# ESP32_led_flasher_3.net
KiCad netlist of a schematic drawn in EAGLE
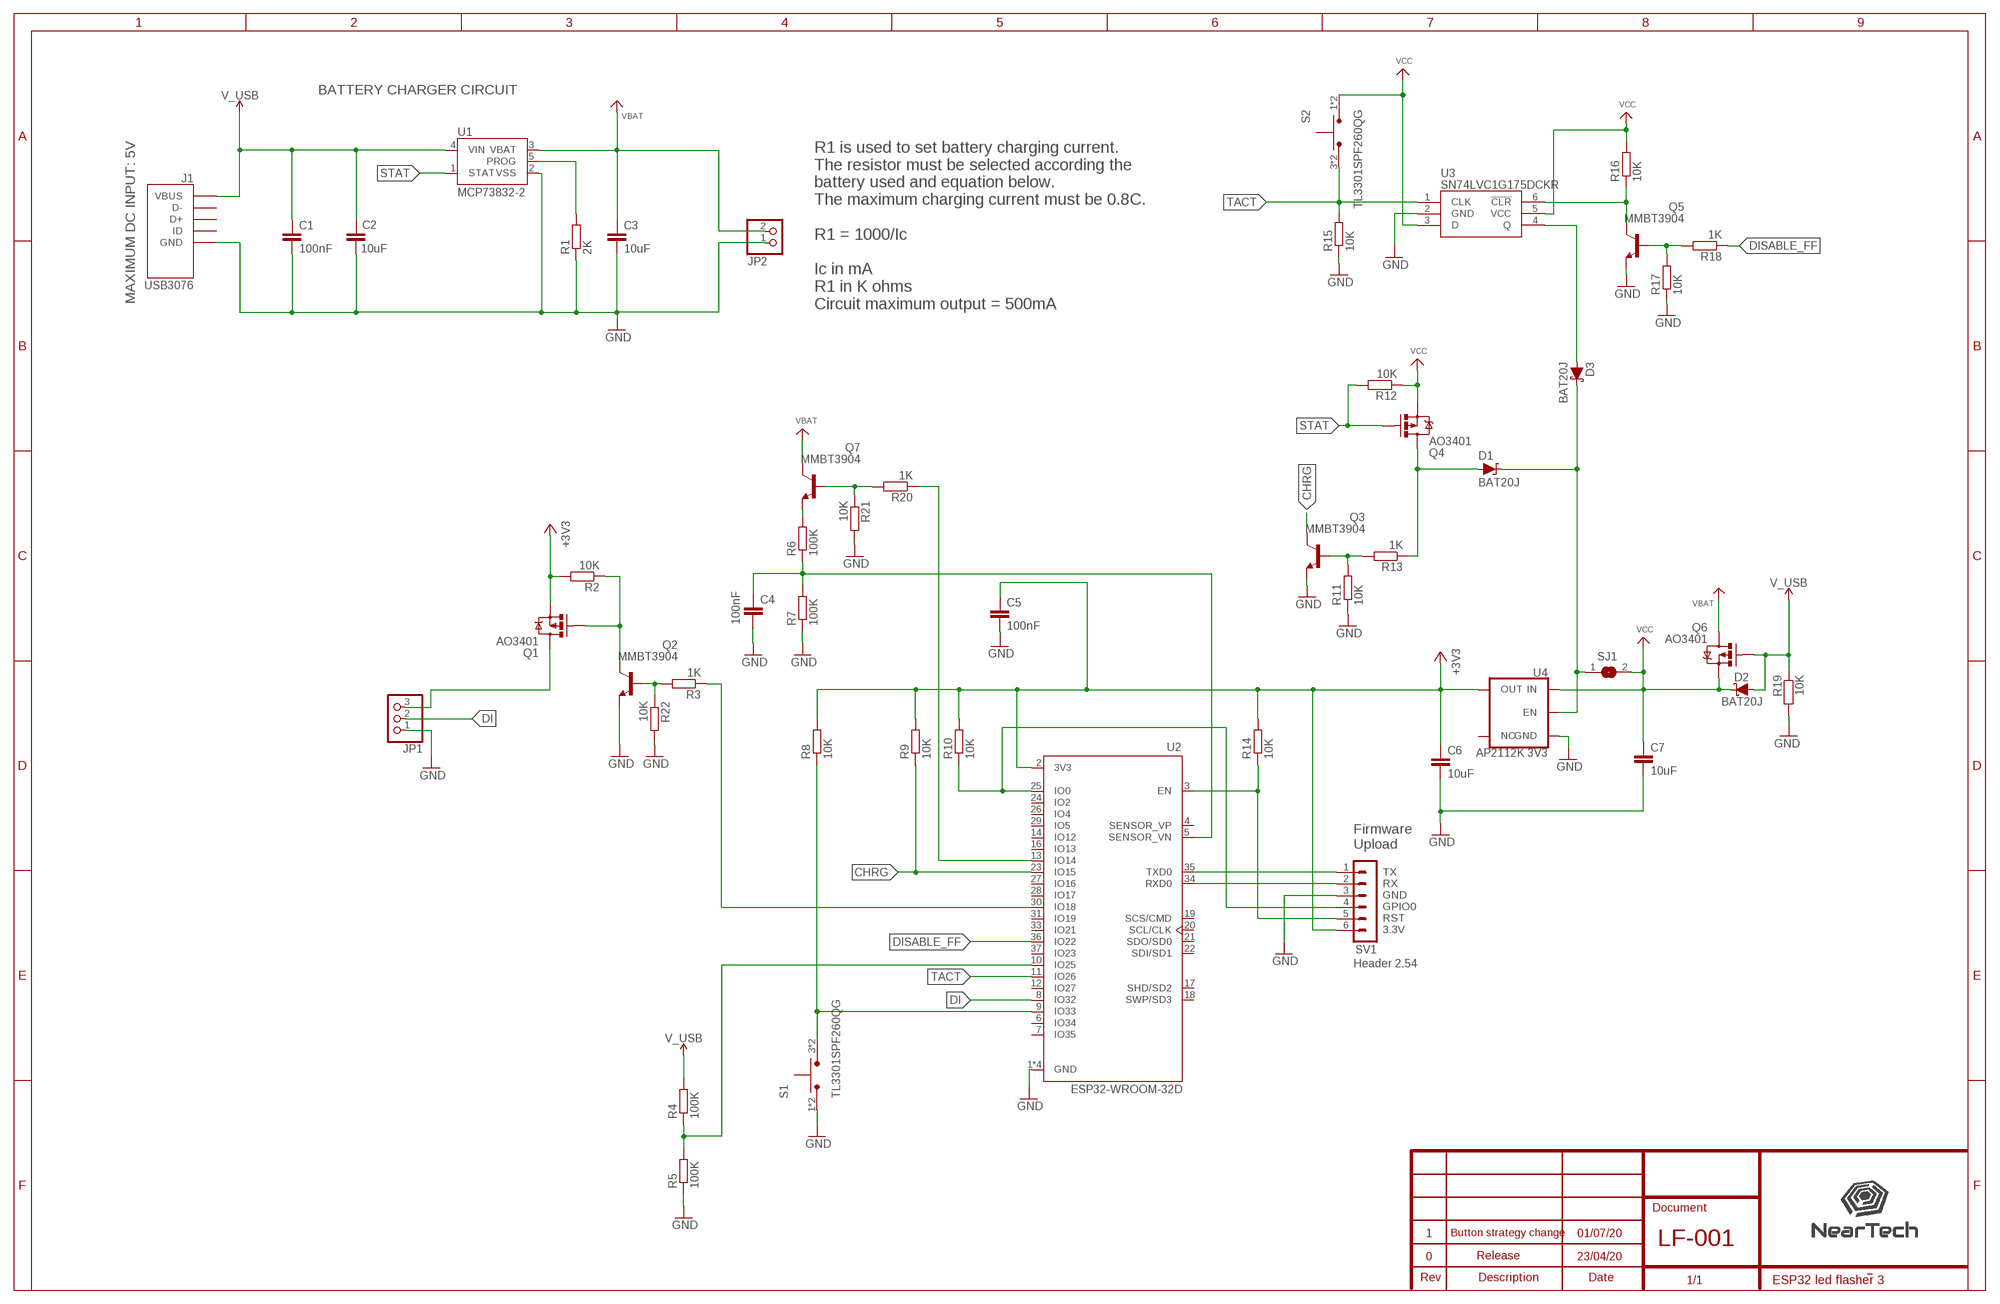
[diagram p0: schematic, sheet 1]

(export (version "E")
  (design (tool "Eeschema 10.0.6"))
  (components
    (comp (ref "C1")
      (value "100nF")
      (footprint "eagle-import:C0402")
      (libsource (lib "eagle-import") (part "rcl_334_C-EUC0402"))
    )
    (comp (ref "C2")
      (value "10uF")
      (footprint "eagle-import:C0603")
      (libsource (lib "eagle-import") (part "C-EUC0603"))
    )
    (comp (ref "C3")
      (value "10uF")
      (footprint "eagle-import:C0603")
      (libsource (lib "eagle-import") (part "rcl_334_C-EUC0603"))
    )
    (comp (ref "C4")
      (value "100nF")
      (footprint "eagle-import:C0402")
      (libsource (lib "eagle-import") (part "rcl_334_C-EUC0402"))
    )
    (comp (ref "C5")
      (value "100nF")
      (footprint "eagle-import:C0402")
      (libsource (lib "eagle-import") (part "rcl_334_C-EUC0402"))
    )
    (comp (ref "C6")
      (value "10uF")
      (footprint "eagle-import:C0603")
      (libsource (lib "eagle-import") (part "C-EUC0603"))
    )
    (comp (ref "C7")
      (value "10uF")
      (footprint "eagle-import:C0603")
      (libsource (lib "eagle-import") (part "rcl_334_C-EUC0603"))
    )
    (comp (ref "D1")
      (value "BAT20J")
      (footprint "eagle-import:SOD-323")
      (libsource (lib "eagle-import") (part "DIODE-SCHOTTKY-BAT20J"))
    )
    (comp (ref "D2")
      (value "BAT20J")
      (footprint "eagle-import:SOD-323")
      (libsource (lib "eagle-import") (part "DIODE-SCHOTTKY-BAT20J"))
    )
    (comp (ref "D3")
      (value "BAT20J")
      (footprint "eagle-import:SOD-323")
      (libsource (lib "eagle-import") (part "DIODE-SCHOTTKY-BAT20J"))
    )
    (comp (ref "J1")
      (value "USB3076")
      (footprint "eagle-import:GCT_USB3076-XX-X_REVC")
      (fields (field (name "MF") "Global Connector Technology") (field (name "MP") "USB3076-30-A"))
      (libsource (lib "eagle-import") (part "USB3076-XX-X_REVC"))
    )
    (comp (ref "JP1")
      (value "PINHD-1X3_2.54")
      (footprint "eagle-import:1X03")
      (libsource (lib "eagle-import") (part "PINHD-1X3_2.54"))
    )
    (comp (ref "JP2")
      (value "PINHD-1X2_2.54")
      (footprint "eagle-import:1X02")
      (libsource (lib "eagle-import") (part "PINHD-1X2_2.54"))
    )
    (comp (ref "Q1")
      (value "AO3401")
      (footprint "eagle-import:SOT23-3@1")
      (libsource (lib "eagle-import") (part "MOSFET-PCHANNELDMG2307L"))
    )
    (comp (ref "Q2")
      (value "MMBT3904")
      (footprint "eagle-import:SOT23")
      (libsource (lib "eagle-import") (part "BCX70SMD"))
    )
    (comp (ref "Q3")
      (value "MMBT3904")
      (footprint "eagle-import:SOT23")
      (libsource (lib "eagle-import") (part "BCX70SMD"))
    )
    (comp (ref "Q4")
      (value "AO3401")
      (footprint "eagle-import:SOT23-3@1")
      (libsource (lib "eagle-import") (part "MOSFET-PCHANNELDMG2307L"))
    )
    (comp (ref "Q5")
      (value "MMBT3904")
      (footprint "eagle-import:SOT23")
      (libsource (lib "eagle-import") (part "BCX70SMD"))
    )
    (comp (ref "Q6")
      (value "AO3401")
      (footprint "eagle-import:SOT23-3@1")
      (libsource (lib "eagle-import") (part "MOSFET-PCHANNELDMG2307L"))
    )
    (comp (ref "Q7")
      (value "MMBT3904")
      (footprint "eagle-import:SOT23")
      (libsource (lib "eagle-import") (part "BCX70SMD"))
    )
    (comp (ref "R1")
      (value "2K")
      (footprint "eagle-import:R0603")
      (libsource (lib "eagle-import") (part "R-EU_R0603"))
    )
    (comp (ref "R2")
      (value "10K")
      (footprint "eagle-import:R0603")
      (libsource (lib "eagle-import") (part "R-EU_R0603"))
    )
    (comp (ref "R3")
      (value "1K")
      (footprint "eagle-import:R0603")
      (libsource (lib "eagle-import") (part "R-EU_R0603"))
    )
    (comp (ref "R4")
      (value "100K")
      (footprint "eagle-import:R0603")
      (libsource (lib "eagle-import") (part "R-EU_R0603"))
    )
    (comp (ref "R5")
      (value "100K")
      (footprint "eagle-import:R0603")
      (libsource (lib "eagle-import") (part "R-EU_R0603"))
    )
    (comp (ref "R6")
      (value "100K")
      (footprint "eagle-import:R0603")
      (libsource (lib "eagle-import") (part "R-EU_R0603"))
    )
    (comp (ref "R7")
      (value "100K")
      (footprint "eagle-import:R0603")
      (libsource (lib "eagle-import") (part "R-EU_R0603"))
    )
    (comp (ref "R8")
      (value "10K")
      (footprint "eagle-import:R0603")
      (libsource (lib "eagle-import") (part "R-EU_R0603"))
    )
    (comp (ref "R9")
      (value "10K")
      (footprint "eagle-import:R0603")
      (libsource (lib "eagle-import") (part "R-EU_R0603"))
    )
    (comp (ref "R10")
      (value "10K")
      (footprint "eagle-import:R0603")
      (libsource (lib "eagle-import") (part "R-EU_R0603"))
    )
    (comp (ref "R11")
      (value "10K")
      (footprint "eagle-import:R0603")
      (libsource (lib "eagle-import") (part "R-EU_R0603"))
    )
    (comp (ref "R12")
      (value "10K")
      (footprint "eagle-import:R0603")
      (libsource (lib "eagle-import") (part "R-EU_R0603"))
    )
    (comp (ref "R13")
      (value "1K")
      (footprint "eagle-import:R0603")
      (libsource (lib "eagle-import") (part "R-EU_R0603"))
    )
    (comp (ref "R14")
      (value "10K")
      (footprint "eagle-import:R0603")
      (libsource (lib "eagle-import") (part "R-EU_R0603"))
    )
    (comp (ref "R15")
      (value "10K")
      (footprint "eagle-import:R0603")
      (libsource (lib "eagle-import") (part "R-EU_R0603"))
    )
    (comp (ref "R16")
      (value "10K")
      (footprint "eagle-import:R0603")
      (libsource (lib "eagle-import") (part "R-EU_R0603"))
    )
    (comp (ref "R17")
      (value "10K")
      (footprint "eagle-import:R0603")
      (libsource (lib "eagle-import") (part "R-EU_R0603"))
    )
    (comp (ref "R18")
      (value "1K")
      (footprint "eagle-import:R0603")
      (libsource (lib "eagle-import") (part "R-EU_R0603"))
    )
    (comp (ref "R19")
      (value "10K")
      (footprint "eagle-import:R0603")
      (libsource (lib "eagle-import") (part "R-EU_R0603"))
    )
    (comp (ref "R20")
      (value "1K")
      (footprint "eagle-import:R0603")
      (libsource (lib "eagle-import") (part "R-EU_R0603"))
    )
    (comp (ref "R21")
      (value "10K")
      (footprint "eagle-import:R0603")
      (libsource (lib "eagle-import") (part "R-EU_R0603"))
    )
    (comp (ref "R22")
      (value "10K")
      (footprint "eagle-import:R0603")
      (libsource (lib "eagle-import") (part "R-EU_R0603"))
    )
    (comp (ref "S1")
      (value "TL3301SPF260QG")
      (footprint "eagle-import:SW_TL3301SPF260QG")
      (fields (field (name "MF") "E-Switch"))
      (libsource (lib "eagle-import") (part "TL3301SPF260QG"))
    )
    (comp (ref "S2")
      (value "TL3301SPF260QG")
      (footprint "eagle-import:SW_TL3301SPF260QG")
      (fields (field (name "MF") "E-Switch"))
      (libsource (lib "eagle-import") (part "TL3301SPF260QG"))
    )
    (comp (ref "SJ1")
      (value "SOLDERJUMPERREFLOW")
      (footprint "eagle-import:SOLDERJUMPER_REFLOW")
      (libsource (lib "eagle-import") (part "SOLDERJUMPERREFLOW"))
    )
    (comp (ref "SV1")
      (value "Header 2.54")
      (footprint "eagle-import:MA06-1")
      (libsource (lib "eagle-import") (part "MA06-1"))
    )
    (comp (ref "U1")
      (value "MCP73832-2")
      (footprint "eagle-import:SOT23-5")
      (libsource (lib "eagle-import") (part "MCP73831"))
    )
    (comp (ref "U2")
      (value "ESP32-WROOM-32D")
      (footprint "eagle-import:MODULE_ESP32-WROOM-32D")
      (fields (field (name "MF") "Espressif Systems"))
      (libsource (lib "eagle-import") (part "ESP32-WROOM-32D"))
    )
    (comp (ref "U3")
      (value "SN74LVC1G175DCKR")
      (footprint "eagle-import:SOP65P210X110-6N")
      (fields (field (name "MOUSER_PART_NUMBER") "595-SN74LVC1G175DCKR"))
      (libsource (lib "eagle-import") (part "SN74LVC1G175DCKR"))
    )
    (comp (ref "U4")
      (value "AP2112K 3V3")
      (footprint "eagle-import:SOT23-5")
      (libsource (lib "eagle-import") (part "V_REG_AP2112K-3.3V"))
    )
  )
  (nets
    (net (code "1") (name "+3V3") (class "Default")
      (node (ref "C5") (pin "1") (pinfunction "1_1") (pintype "passive"))
      (node (ref "C6") (pin "1") (pinfunction "1_1") (pintype "passive"))
      (node (ref "Q1") (pin "2") (pinfunction "S_2") (pintype "passive"))
      (node (ref "R10") (pin "2") (pinfunction "2_2") (pintype "passive"))
      (node (ref "R14") (pin "2") (pinfunction "2_2") (pintype "passive"))
      (node (ref "R2") (pin "2") (pinfunction "2_2") (pintype "passive"))
      (node (ref "R8") (pin "2") (pinfunction "2_2") (pintype "passive"))
      (node (ref "R9") (pin "2") (pinfunction "2_2") (pintype "passive"))
      (node (ref "SV1") (pin "6") (pinfunction "6_6") (pintype "passive"))
      (node (ref "U2") (pin "2") (pinfunction "3V3_2") (pintype "power_in"))
      (node (ref "U4") (pin "5") (pinfunction "OUT_5") (pintype "passive"))
    )
    (net (code "2") (name "CHRG") (class "Default")
      (node (ref "Q3") (pin "3") (pinfunction "C_3") (pintype "passive"))
      (node (ref "R9") (pin "1") (pinfunction "1_1") (pintype "passive"))
      (node (ref "U2") (pin "23") (pinfunction "IO15_23") (pintype "bidirectional"))
    )
    (net (code "3") (name "DI") (class "Default")
      (node (ref "JP1") (pin "2") (pinfunction "2_2") (pintype "passive"))
      (node (ref "U2") (pin "8") (pinfunction "IO32_8") (pintype "bidirectional"))
    )
    (net (code "4") (name "DISABLE_FF") (class "Default")
      (node (ref "R18") (pin "1") (pinfunction "1_1") (pintype "passive"))
      (node (ref "U2") (pin "36") (pinfunction "IO22_36") (pintype "bidirectional"))
    )
    (net (code "5") (name "GND") (class "Default")
      (node (ref "C1") (pin "2") (pinfunction "2_2") (pintype "passive"))
      (node (ref "C2") (pin "2") (pinfunction "2_2") (pintype "passive"))
      (node (ref "C3") (pin "2") (pinfunction "2_2") (pintype "passive"))
      (node (ref "C4") (pin "2") (pinfunction "2_2") (pintype "passive"))
      (node (ref "C5") (pin "2") (pinfunction "2_2") (pintype "passive"))
      (node (ref "C6") (pin "2") (pinfunction "2_2") (pintype "passive"))
      (node (ref "C7") (pin "2") (pinfunction "2_2") (pintype "passive"))
      (node (ref "J1") (pin "5") (pinfunction "GND_5") (pintype "power_in"))
      (node (ref "JP1") (pin "1") (pinfunction "1_1") (pintype "passive"))
      (node (ref "JP2") (pin "1") (pinfunction "1_1") (pintype "passive"))
      (node (ref "Q2") (pin "2") (pinfunction "E_2") (pintype "passive"))
      (node (ref "Q3") (pin "2") (pinfunction "E_2") (pintype "passive"))
      (node (ref "Q5") (pin "2") (pinfunction "E_2") (pintype "passive"))
      (node (ref "R1") (pin "1") (pinfunction "1_1") (pintype "passive"))
      (node (ref "R11") (pin "1") (pinfunction "1_1") (pintype "passive"))
      (node (ref "R15") (pin "1") (pinfunction "1_1") (pintype "passive"))
      (node (ref "R17") (pin "1") (pinfunction "1_1") (pintype "passive"))
      (node (ref "R19") (pin "2") (pinfunction "2_2") (pintype "passive"))
      (node (ref "R21") (pin "2") (pinfunction "2_2") (pintype "passive"))
      (node (ref "R22") (pin "2") (pinfunction "2_2") (pintype "passive"))
      (node (ref "R5") (pin "1") (pinfunction "1_1") (pintype "passive"))
      (node (ref "R7") (pin "1") (pinfunction "1_1") (pintype "passive"))
      (node (ref "S1") (pin "1") (pinfunction "1_1") (pintype "passive"))
      (node (ref "S1") (pin "2") (pinfunction "1_2") (pintype "passive"))
      (node (ref "SV1") (pin "3") (pinfunction "3_3") (pintype "passive"))
      (node (ref "U1") (pin "2") (pinfunction "VSS_2") (pintype "power_in"))
      (node (ref "U2") (pin "1") (pinfunction "GND_1") (pintype "power_in"))
      (node (ref "U2") (pin "15") (pinfunction "GND_15") (pintype "power_in"))
      (node (ref "U2") (pin "38") (pinfunction "GND_38") (pintype "power_in"))
      (node (ref "U2") (pin "39") (pinfunction "GND_39") (pintype "power_in"))
      (node (ref "U3") (pin "2") (pinfunction "GND_2") (pintype "bidirectional"))
      (node (ref "U4") (pin "2") (pinfunction "GND_2") (pintype "input"))
    )
    (net (code "6") (name "Net-(Q1-D)") (class "Default")
      (node (ref "JP1") (pin "3") (pinfunction "3_3") (pintype "passive"))
      (node (ref "Q1") (pin "3") (pinfunction "D_3") (pintype "passive"))
    )
    (net (code "7") (name "Net-(Q1-G)") (class "Default")
      (node (ref "Q1") (pin "1") (pinfunction "G_1") (pintype "passive"))
      (node (ref "Q2") (pin "3") (pinfunction "C_3") (pintype "passive"))
      (node (ref "R2") (pin "1") (pinfunction "1_1") (pintype "passive"))
    )
    (net (code "8") (name "Net-(Q2-B)") (class "Default")
      (node (ref "Q2") (pin "1") (pinfunction "B_1") (pintype "passive"))
      (node (ref "R22") (pin "1") (pinfunction "1_1") (pintype "passive"))
      (node (ref "R3") (pin "2") (pinfunction "2_2") (pintype "passive"))
    )
    (net (code "9") (name "Net-(Q3-B)") (class "Default")
      (node (ref "Q3") (pin "1") (pinfunction "B_1") (pintype "passive"))
      (node (ref "R11") (pin "2") (pinfunction "2_2") (pintype "passive"))
      (node (ref "R13") (pin "2") (pinfunction "2_2") (pintype "passive"))
    )
    (net (code "10") (name "Net-(Q4-D)") (class "Default")
      (node (ref "D1") (pin "A") (pinfunction "A_A") (pintype "passive"))
      (node (ref "Q4") (pin "3") (pinfunction "D_3") (pintype "passive"))
      (node (ref "R13") (pin "1") (pinfunction "1_1") (pintype "passive"))
    )
    (net (code "11") (name "Net-(Q5-B)") (class "Default")
      (node (ref "Q5") (pin "1") (pinfunction "B_1") (pintype "passive"))
      (node (ref "R17") (pin "2") (pinfunction "2_2") (pintype "passive"))
      (node (ref "R18") (pin "2") (pinfunction "2_2") (pintype "passive"))
    )
    (net (code "12") (name "Net-(Q5-C)") (class "Default")
      (node (ref "Q5") (pin "3") (pinfunction "C_3") (pintype "passive"))
      (node (ref "R16") (pin "1") (pinfunction "1_1") (pintype "passive"))
      (node (ref "U3") (pin "6") (pinfunction "~{CLR}_6") (pintype "bidirectional"))
    )
    (net (code "13") (name "Net-(Q7-B)") (class "Default")
      (node (ref "Q7") (pin "1") (pinfunction "B_1") (pintype "passive"))
      (node (ref "R20") (pin "2") (pinfunction "2_2") (pintype "passive"))
      (node (ref "R21") (pin "1") (pinfunction "1_1") (pintype "passive"))
    )
    (net (code "14") (name "Net-(Q7-E)") (class "Default")
      (node (ref "Q7") (pin "2") (pinfunction "E_2") (pintype "passive"))
      (node (ref "R6") (pin "2") (pinfunction "2_2") (pintype "passive"))
    )
    (net (code "15") (name "Net-(U1-PROG)") (class "Default")
      (node (ref "R1") (pin "2") (pinfunction "2_2") (pintype "passive"))
      (node (ref "U1") (pin "5") (pinfunction "PROG_5") (pintype "input"))
    )
    (net (code "16") (name "Net-(U2-EN)") (class "Default")
      (node (ref "R14") (pin "1") (pinfunction "1_1") (pintype "passive"))
      (node (ref "SV1") (pin "5") (pinfunction "5_5") (pintype "passive"))
      (node (ref "U2") (pin "3") (pinfunction "EN_3") (pintype "input"))
    )
    (net (code "17") (name "Net-(U2-IO0)") (class "Default")
      (node (ref "R10") (pin "1") (pinfunction "1_1") (pintype "passive"))
      (node (ref "SV1") (pin "4") (pinfunction "4_4") (pintype "passive"))
      (node (ref "U2") (pin "25") (pinfunction "IO0_25") (pintype "bidirectional"))
    )
    (net (code "18") (name "Net-(U2-IO14)") (class "Default")
      (node (ref "R20") (pin "1") (pinfunction "1_1") (pintype "passive"))
      (node (ref "U2") (pin "13") (pinfunction "IO14_13") (pintype "bidirectional"))
    )
    (net (code "19") (name "Net-(U2-IO18)") (class "Default")
      (node (ref "R3") (pin "1") (pinfunction "1_1") (pintype "passive"))
      (node (ref "U2") (pin "30") (pinfunction "IO18_30") (pintype "bidirectional"))
    )
    (net (code "20") (name "Net-(U2-IO25)") (class "Default")
      (node (ref "R4") (pin "1") (pinfunction "1_1") (pintype "passive"))
      (node (ref "R5") (pin "2") (pinfunction "2_2") (pintype "passive"))
      (node (ref "U2") (pin "10") (pinfunction "IO25_10") (pintype "bidirectional"))
    )
    (net (code "21") (name "Net-(U2-IO33)") (class "Default")
      (node (ref "R8") (pin "1") (pinfunction "1_1") (pintype "passive"))
      (node (ref "S1") (pin "3") (pinfunction "2_3") (pintype "passive"))
      (node (ref "S1") (pin "4") (pinfunction "2_4") (pintype "passive"))
      (node (ref "U2") (pin "9") (pinfunction "IO33_9") (pintype "bidirectional"))
    )
    (net (code "22") (name "Net-(U2-RXD0)") (class "Default")
      (node (ref "SV1") (pin "2") (pinfunction "2_2") (pintype "passive"))
      (node (ref "U2") (pin "34") (pinfunction "RXD0_34") (pintype "bidirectional"))
    )
    (net (code "23") (name "Net-(U2-SENSOR_VN)") (class "Default")
      (node (ref "C4") (pin "1") (pinfunction "1_1") (pintype "passive"))
      (node (ref "R6") (pin "1") (pinfunction "1_1") (pintype "passive"))
      (node (ref "R7") (pin "2") (pinfunction "2_2") (pintype "passive"))
      (node (ref "U2") (pin "5") (pinfunction "SENSOR_VN_5") (pintype "input"))
    )
    (net (code "24") (name "Net-(U2-TXD0)") (class "Default")
      (node (ref "SV1") (pin "1") (pinfunction "1_1") (pintype "passive"))
      (node (ref "U2") (pin "35") (pinfunction "TXD0_35") (pintype "bidirectional"))
    )
    (net (code "25") (name "Net-(U3-Q)") (class "Default")
      (node (ref "D3") (pin "A") (pinfunction "A_A") (pintype "passive"))
      (node (ref "U3") (pin "4") (pinfunction "Q_4") (pintype "bidirectional"))
    )
    (net (code "26") (name "Net-(U4-EN)") (class "Default")
      (node (ref "D1") (pin "C") (pinfunction "C_C") (pintype "passive"))
      (node (ref "D3") (pin "C") (pinfunction "C_C") (pintype "passive"))
      (node (ref "SJ1") (pin "1") (pinfunction "1_1") (pintype "passive"))
      (node (ref "U4") (pin "3") (pinfunction "EN_3") (pintype "input"))
    )
    (net (code "27") (name "STAT") (class "Default")
      (node (ref "Q4") (pin "1") (pinfunction "G_1") (pintype "passive"))
      (node (ref "R12") (pin "2") (pinfunction "2_2") (pintype "passive"))
      (node (ref "U1") (pin "1") (pinfunction "STAT_1") (pintype "output"))
    )
    (net (code "28") (name "TACT") (class "Default")
      (node (ref "R15") (pin "2") (pinfunction "2_2") (pintype "passive"))
      (node (ref "S2") (pin "3") (pinfunction "2_3") (pintype "passive"))
      (node (ref "S2") (pin "4") (pinfunction "2_4") (pintype "passive"))
      (node (ref "U2") (pin "11") (pinfunction "IO26_11") (pintype "bidirectional"))
      (node (ref "U3") (pin "1") (pinfunction "CLK_1") (pintype "bidirectional"))
    )
    (net (code "29") (name "VBAT") (class "Default")
      (node (ref "C3") (pin "1") (pinfunction "1_1") (pintype "passive"))
      (node (ref "JP2") (pin "2") (pinfunction "2_2") (pintype "passive"))
      (node (ref "Q6") (pin "3") (pinfunction "D_3") (pintype "passive"))
      (node (ref "Q7") (pin "3") (pinfunction "C_3") (pintype "passive"))
      (node (ref "U1") (pin "3") (pinfunction "VBAT_3") (pintype "power_in"))
    )
    (net (code "30") (name "VCC") (class "Default")
      (node (ref "C7") (pin "1") (pinfunction "1_1") (pintype "passive"))
      (node (ref "D2") (pin "C") (pinfunction "C_C") (pintype "passive"))
      (node (ref "Q4") (pin "2") (pinfunction "S_2") (pintype "passive"))
      (node (ref "Q6") (pin "2") (pinfunction "S_2") (pintype "passive"))
      (node (ref "R12") (pin "1") (pinfunction "1_1") (pintype "passive"))
      (node (ref "R16") (pin "2") (pinfunction "2_2") (pintype "passive"))
      (node (ref "S2") (pin "1") (pinfunction "1_1") (pintype "passive"))
      (node (ref "S2") (pin "2") (pinfunction "1_2") (pintype "passive"))
      (node (ref "SJ1") (pin "2") (pinfunction "2_2") (pintype "passive"))
      (node (ref "U3") (pin "3") (pinfunction "D_3") (pintype "bidirectional"))
      (node (ref "U3") (pin "5") (pinfunction "VCC_5") (pintype "bidirectional"))
      (node (ref "U4") (pin "1") (pinfunction "IN_1") (pintype "input"))
    )
    (net (code "31") (name "V_USB") (class "Default")
      (node (ref "C1") (pin "1") (pinfunction "1_1") (pintype "passive"))
      (node (ref "C2") (pin "1") (pinfunction "1_1") (pintype "passive"))
      (node (ref "D2") (pin "A") (pinfunction "A_A") (pintype "passive"))
      (node (ref "J1") (pin "1") (pinfunction "VBUS_1") (pintype "power_in"))
      (node (ref "Q6") (pin "1") (pinfunction "G_1") (pintype "passive"))
      (node (ref "R19") (pin "1") (pinfunction "1_1") (pintype "passive"))
      (node (ref "R4") (pin "2") (pinfunction "2_2") (pintype "passive"))
      (node (ref "U1") (pin "4") (pinfunction "VIN_4") (pintype "power_in"))
    )
    (net (code "32") (name "unconnected-(J1-D+-Pad3)") (class "Default")
      (node (ref "J1") (pin "3") (pinfunction "D+_3") (pintype "bidirectional"))
    )
    (net (code "33") (name "unconnected-(J1-D--Pad2)") (class "Default")
      (node (ref "J1") (pin "2") (pinfunction "D-_2") (pintype "bidirectional"))
    )
    (net (code "34") (name "unconnected-(J1-ID-Pad4)") (class "Default")
      (node (ref "J1") (pin "4") (pinfunction "ID_4") (pintype "bidirectional"))
    )
    (net (code "35") (name "unconnected-(U2-IO2-Pad24)") (class "Default")
      (node (ref "U2") (pin "24") (pinfunction "IO2_24") (pintype "bidirectional"))
    )
    (net (code "36") (name "unconnected-(U2-IO4-Pad26)") (class "Default")
      (node (ref "U2") (pin "26") (pinfunction "IO4_26") (pintype "bidirectional"))
    )
    (net (code "37") (name "unconnected-(U2-IO5-Pad29)") (class "Default")
      (node (ref "U2") (pin "29") (pinfunction "IO5_29") (pintype "bidirectional"))
    )
    (net (code "38") (name "unconnected-(U2-IO12-Pad14)") (class "Default")
      (node (ref "U2") (pin "14") (pinfunction "IO12_14") (pintype "bidirectional"))
    )
    (net (code "39") (name "unconnected-(U2-IO13-Pad16)") (class "Default")
      (node (ref "U2") (pin "16") (pinfunction "IO13_16") (pintype "bidirectional"))
    )
    (net (code "40") (name "unconnected-(U2-IO16-Pad27)") (class "Default")
      (node (ref "U2") (pin "27") (pinfunction "IO16_27") (pintype "bidirectional"))
    )
    (net (code "41") (name "unconnected-(U2-IO17-Pad28)") (class "Default")
      (node (ref "U2") (pin "28") (pinfunction "IO17_28") (pintype "bidirectional"))
    )
    (net (code "42") (name "unconnected-(U2-IO19-Pad31)") (class "Default")
      (node (ref "U2") (pin "31") (pinfunction "IO19_31") (pintype "bidirectional"))
    )
    (net (code "43") (name "unconnected-(U2-IO21-Pad33)") (class "Default")
      (node (ref "U2") (pin "33") (pinfunction "IO21_33") (pintype "bidirectional"))
    )
    (net (code "44") (name "unconnected-(U2-IO23-Pad37)") (class "Default")
      (node (ref "U2") (pin "37") (pinfunction "IO23_37") (pintype "bidirectional"))
    )
    (net (code "45") (name "unconnected-(U2-IO27-Pad12)") (class "Default")
      (node (ref "U2") (pin "12") (pinfunction "IO27_12") (pintype "bidirectional"))
    )
    (net (code "46") (name "unconnected-(U2-IO34-Pad6)") (class "Default")
      (node (ref "U2") (pin "6") (pinfunction "IO34_6") (pintype "bidirectional"))
    )
    (net (code "47") (name "unconnected-(U2-IO35-Pad7)") (class "Default")
      (node (ref "U2") (pin "7") (pinfunction "IO35_7") (pintype "bidirectional"))
    )
    (net (code "48") (name "unconnected-(U2-SCL{slash}CLK-Pad20)") (class "Default")
      (node (ref "U2") (pin "20") (pinfunction "SCL/CLK_20") (pintype "bidirectional"))
    )
    (net (code "49") (name "unconnected-(U2-SCS{slash}CMD-Pad19)") (class "Default")
      (node (ref "U2") (pin "19") (pinfunction "SCS/CMD_19") (pintype "bidirectional"))
    )
    (net (code "50") (name "unconnected-(U2-SDI{slash}SD1-Pad22)") (class "Default")
      (node (ref "U2") (pin "22") (pinfunction "SDI/SD1_22") (pintype "bidirectional"))
    )
    (net (code "51") (name "unconnected-(U2-SDO{slash}SD0-Pad21)") (class "Default")
      (node (ref "U2") (pin "21") (pinfunction "SDO/SD0_21") (pintype "bidirectional"))
    )
    (net (code "52") (name "unconnected-(U2-SENSOR_VP-Pad4)") (class "Default")
      (node (ref "U2") (pin "4") (pinfunction "SENSOR_VP_4") (pintype "input"))
    )
    (net (code "53") (name "unconnected-(U2-SHD{slash}SD2-Pad17)") (class "Default")
      (node (ref "U2") (pin "17") (pinfunction "SHD/SD2_17") (pintype "bidirectional"))
    )
    (net (code "54") (name "unconnected-(U2-SWP{slash}SD3-Pad18)") (class "Default")
      (node (ref "U2") (pin "18") (pinfunction "SWP/SD3_18") (pintype "bidirectional"))
    )
    (net (code "55") (name "unconnected-(U4-NC-Pad4)") (class "Default")
      (node (ref "U4") (pin "4") (pinfunction "NC_4") (pintype "no_connect"))
    )
  )
)
